# RTC.net
KiCad netlist of a schematic drawn in Altium Designer
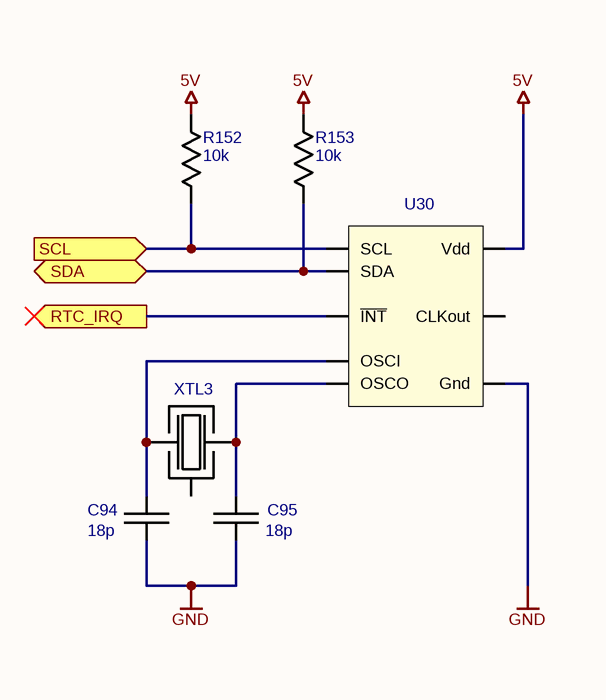
[diagram p0: RTC.SchDoc]

(export (version "E")
  (design (tool "Eeschema 10.0.6"))
  (components
    (comp (ref "C94")
      (value "18p")
      (footprint "CAP CER 0603 NP")
      (description "CC0603JRNPO9BN180")
      (libsource (lib "levin") (part "Capacitor"))
    )
    (comp (ref "C95")
      (value "18p")
      (footprint "CAP CER 0603 NP")
      (description "CC0603JRNPO9BN180")
      (libsource (lib "levin") (part "Capacitor"))
    )
    (comp (ref "R152")
      (value "10k")
      (footprint "RES 0603")
      (description "RC0603FR-0710KL")
      (libsource (lib "levin") (part "Resistor"))
    )
    (comp (ref "R153")
      (value "10k")
      (footprint "RES 0603")
      (description "RC0603FR-0710KL")
      (libsource (lib "levin") (part "Resistor"))
    )
    (comp (ref "U30")
      (value "Real-Time Clock IC")
      (footprint "SOIC-8")
      (description "PCF8563T/5,518")
      (libsource (lib "levin") (part "PCF8653"))
    )
    (comp (ref "XTL3")
      (value "32.768 kHz")
      (footprint "XTAL KX-327NHT")
      (description "12.87150")
      (libsource (lib "levin") (part "Quartz Resonator"))
    )
  )
  (nets
    (net (code "1") (name "/RTC_IRQ") (class "Default")
      (node (ref "U30") (pin "3") (pinfunction "~{INT}_3") (pintype "passive"))
    )
    (net (code "2") (name "/SCL") (class "Default")
      (node (ref "R152") (pin "1") (pinfunction "1_1") (pintype "passive"))
      (node (ref "U30") (pin "6") (pinfunction "SCL_6") (pintype "passive"))
    )
    (net (code "3") (name "/SDA") (class "Default")
      (node (ref "R153") (pin "1") (pinfunction "1_1") (pintype "passive"))
      (node (ref "U30") (pin "5") (pinfunction "SDA_5") (pintype "passive"))
    )
    (net (code "4") (name "5V") (class "Default")
      (node (ref "R152") (pin "2") (pinfunction "2_2") (pintype "passive"))
      (node (ref "R153") (pin "2") (pinfunction "2_2") (pintype "passive"))
      (node (ref "U30") (pin "8") (pinfunction "Vdd_8") (pintype "passive"))
    )
    (net (code "5") (name "GND") (class "Default")
      (node (ref "C94") (pin "1") (pinfunction "1_1") (pintype "passive"))
      (node (ref "C95") (pin "1") (pinfunction "1_1") (pintype "passive"))
      (node (ref "U30") (pin "4") (pinfunction "Gnd_4") (pintype "passive"))
    )
    (net (code "6") (name "Net-(U30-OSCI)") (class "Default")
      (node (ref "C94") (pin "2") (pinfunction "2_2") (pintype "passive"))
      (node (ref "U30") (pin "1") (pinfunction "OSCI_1") (pintype "passive"))
      (node (ref "XTL3") (pin "1") (pinfunction "1_1") (pintype "passive"))
    )
    (net (code "7") (name "Net-(U30-OSCO)") (class "Default")
      (node (ref "C95") (pin "2") (pinfunction "2_2") (pintype "passive"))
      (node (ref "U30") (pin "2") (pinfunction "OSCO_2") (pintype "passive"))
      (node (ref "XTL3") (pin "3") (pinfunction "3_3") (pintype "passive"))
    )
    (net (code "8") (name "unconnected-(U30-CLKout-Pad7)") (class "Default")
      (node (ref "U30") (pin "7") (pinfunction "CLKout_7") (pintype "passive"))
    )
    (net (code "9") (name "unconnected-(XTL3-Pad2)") (class "Default")
      (node (ref "XTL3") (pin "2") (pinfunction "2_2") (pintype "passive"))
    )
  )
)
